# mm8i.net
KiCad netlist of a schematic drawn in EAGLE
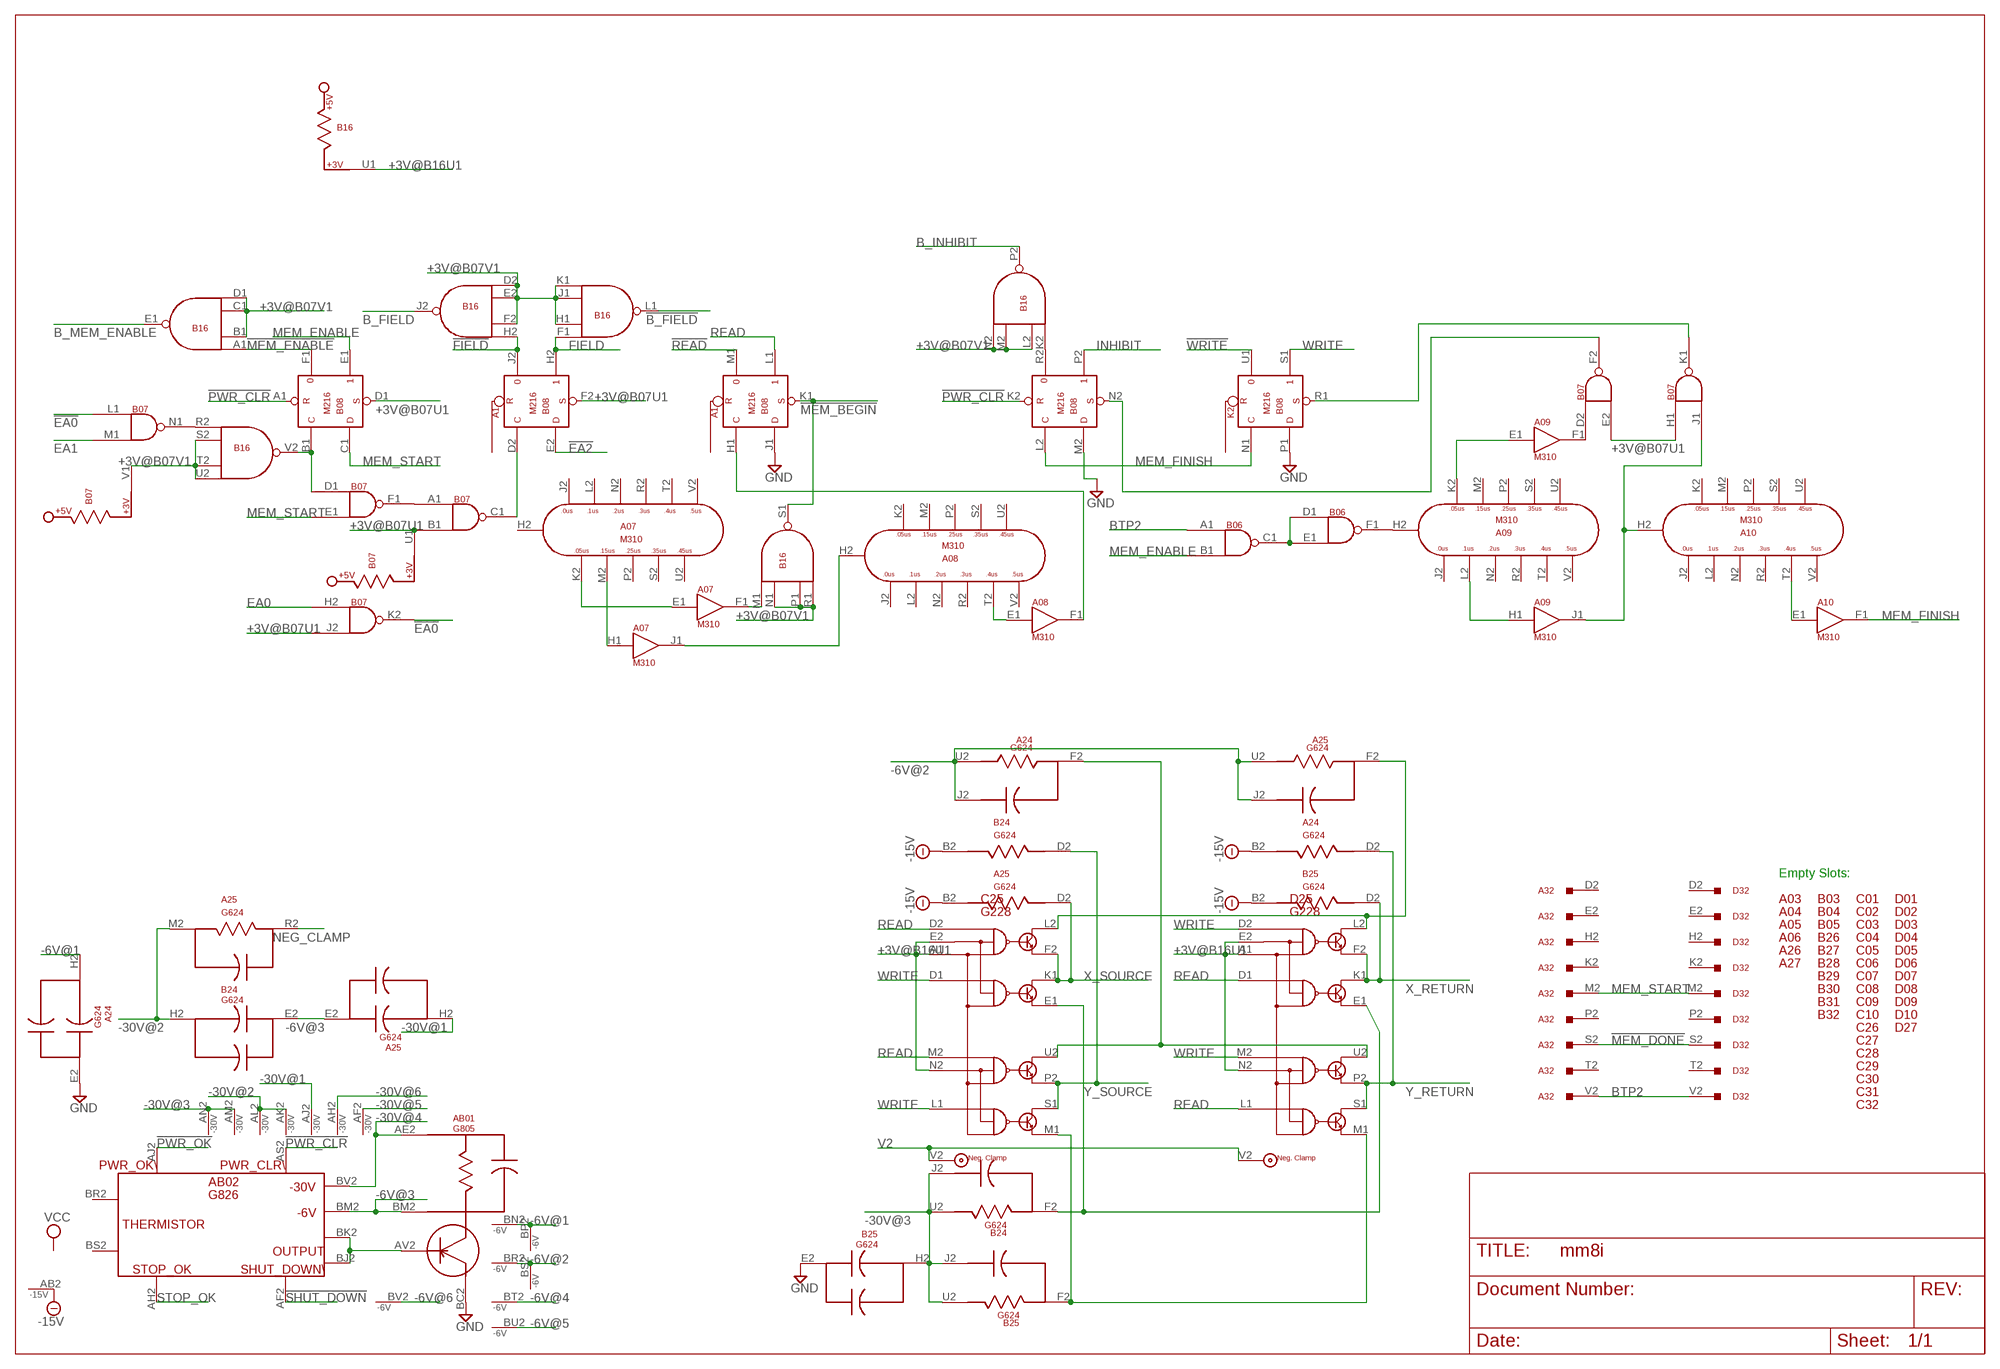
[diagram p0: schematic, sheet 1]

(export (version "E")
  (design (tool "Eeschema 10.0.6"))
  (components
    (comp (ref "A03")
      (value "H807")
      (footprint "eagle-import:H807")
      (libsource (lib "eagle-import") (part "H807"))
    )
    (comp (ref "A04")
      (value "H807")
      (footprint "eagle-import:H807")
      (libsource (lib "eagle-import") (part "H807"))
    )
    (comp (ref "A05")
      (value "H807")
      (footprint "eagle-import:H807")
      (libsource (lib "eagle-import") (part "H807"))
    )
    (comp (ref "A06")
      (value "H807")
      (footprint "eagle-import:H807")
      (libsource (lib "eagle-import") (part "H807"))
    )
    (comp (ref "A07")
      (value "M310")
      (footprint "eagle-import:H807")
      (libsource (lib "eagle-import") (part "M310"))
    )
    (comp (ref "A08")
      (value "M310")
      (footprint "eagle-import:H807")
      (libsource (lib "eagle-import") (part "M310"))
    )
    (comp (ref "A09")
      (value "M310")
      (footprint "eagle-import:H807")
      (libsource (lib "eagle-import") (part "M310"))
    )
    (comp (ref "A10")
      (value "M310")
      (footprint "eagle-import:H807")
      (libsource (lib "eagle-import") (part "M310"))
    )
    (comp (ref "A24")
      (value "G624")
      (footprint "eagle-import:H807")
      (libsource (lib "eagle-import") (part "G624"))
    )
    (comp (ref "A25")
      (value "G624")
      (footprint "eagle-import:H807")
      (libsource (lib "eagle-import") (part "G624"))
    )
    (comp (ref "A26")
      (value "H807")
      (footprint "eagle-import:H807")
      (libsource (lib "eagle-import") (part "H807"))
    )
    (comp (ref "A27")
      (value "H807")
      (footprint "eagle-import:H807")
      (libsource (lib "eagle-import") (part "H807"))
    )
    (comp (ref "A32")
      (value "W033")
      (footprint "eagle-import:H807")
      (libsource (lib "eagle-import") (part "W011"))
    )
    (comp (ref "AB01")
      (value "G805")
      (footprint "eagle-import:H807-2")
      (libsource (lib "eagle-import") (part "G805"))
    )
    (comp (ref "AB02")
      (value "G826")
      (footprint "eagle-import:H807-2")
      (libsource (lib "eagle-import") (part "G826"))
    )
    (comp (ref "B03")
      (value "H807")
      (footprint "eagle-import:H807")
      (libsource (lib "eagle-import") (part "H807"))
    )
    (comp (ref "B04")
      (value "H807")
      (footprint "eagle-import:H807")
      (libsource (lib "eagle-import") (part "H807"))
    )
    (comp (ref "B05")
      (value "H807")
      (footprint "eagle-import:H807")
      (libsource (lib "eagle-import") (part "H807"))
    )
    (comp (ref "B06")
      (value "M113")
      (footprint "eagle-import:H807")
      (libsource (lib "eagle-import") (part "M113"))
    )
    (comp (ref "B07")
      (value "M113")
      (footprint "eagle-import:H807")
      (libsource (lib "eagle-import") (part "M113"))
    )
    (comp (ref "B08")
      (value "M216")
      (footprint "eagle-import:H807")
      (libsource (lib "eagle-import") (part "M206X"))
    )
    (comp (ref "B16")
      (value "M617")
      (footprint "eagle-import:H807")
      (libsource (lib "eagle-import") (part "M617"))
    )
    (comp (ref "B24")
      (value "G624")
      (footprint "eagle-import:H807")
      (libsource (lib "eagle-import") (part "G624"))
    )
    (comp (ref "B25")
      (value "G624")
      (footprint "eagle-import:H807")
      (libsource (lib "eagle-import") (part "G624"))
    )
    (comp (ref "B26")
      (value "H807")
      (footprint "eagle-import:H807")
      (libsource (lib "eagle-import") (part "H807"))
    )
    (comp (ref "B27")
      (value "H807")
      (footprint "eagle-import:H807")
      (libsource (lib "eagle-import") (part "H807"))
    )
    (comp (ref "B28")
      (value "H807")
      (footprint "eagle-import:H807")
      (libsource (lib "eagle-import") (part "H807"))
    )
    (comp (ref "B29")
      (value "H807")
      (footprint "eagle-import:H807")
      (libsource (lib "eagle-import") (part "H807"))
    )
    (comp (ref "B30")
      (value "H807")
      (footprint "eagle-import:H807")
      (libsource (lib "eagle-import") (part "H807"))
    )
    (comp (ref "B31")
      (value "H807")
      (footprint "eagle-import:H807")
      (libsource (lib "eagle-import") (part "H807"))
    )
    (comp (ref "B32")
      (value "H807")
      (footprint "eagle-import:H807")
      (libsource (lib "eagle-import") (part "H807"))
    )
    (comp (ref "C01")
      (value "H807")
      (footprint "eagle-import:H807")
      (libsource (lib "eagle-import") (part "H807"))
    )
    (comp (ref "C02")
      (value "H807")
      (footprint "eagle-import:H807")
      (libsource (lib "eagle-import") (part "H807"))
    )
    (comp (ref "C03")
      (value "H807")
      (footprint "eagle-import:H807")
      (libsource (lib "eagle-import") (part "H807"))
    )
    (comp (ref "C04")
      (value "H807")
      (footprint "eagle-import:H807")
      (libsource (lib "eagle-import") (part "H807"))
    )
    (comp (ref "C05")
      (value "H807")
      (footprint "eagle-import:H807")
      (libsource (lib "eagle-import") (part "H807"))
    )
    (comp (ref "C06")
      (value "H807")
      (footprint "eagle-import:H807")
      (libsource (lib "eagle-import") (part "H807"))
    )
    (comp (ref "C07")
      (value "H807")
      (footprint "eagle-import:H807")
      (libsource (lib "eagle-import") (part "H807"))
    )
    (comp (ref "C08")
      (value "H807")
      (footprint "eagle-import:H807")
      (libsource (lib "eagle-import") (part "H807"))
    )
    (comp (ref "C09")
      (value "H807")
      (footprint "eagle-import:H807")
      (libsource (lib "eagle-import") (part "H807"))
    )
    (comp (ref "C10")
      (value "H807")
      (footprint "eagle-import:H807")
      (libsource (lib "eagle-import") (part "H807"))
    )
    (comp (ref "C25")
      (value "G228")
      (footprint "eagle-import:H807")
      (libsource (lib "eagle-import") (part "G228"))
    )
    (comp (ref "C26")
      (value "H807")
      (footprint "eagle-import:H807")
      (libsource (lib "eagle-import") (part "H807"))
    )
    (comp (ref "C27")
      (value "H807")
      (footprint "eagle-import:H807")
      (libsource (lib "eagle-import") (part "H807"))
    )
    (comp (ref "C28")
      (value "H807")
      (footprint "eagle-import:H807")
      (libsource (lib "eagle-import") (part "H807"))
    )
    (comp (ref "C29")
      (value "H807")
      (footprint "eagle-import:H807")
      (libsource (lib "eagle-import") (part "H807"))
    )
    (comp (ref "C30")
      (value "H807")
      (footprint "eagle-import:H807")
      (libsource (lib "eagle-import") (part "H807"))
    )
    (comp (ref "C31")
      (value "H807")
      (footprint "eagle-import:H807")
      (libsource (lib "eagle-import") (part "H807"))
    )
    (comp (ref "C32")
      (value "H807")
      (footprint "eagle-import:H807")
      (libsource (lib "eagle-import") (part "H807"))
    )
    (comp (ref "D01")
      (value "H807")
      (footprint "eagle-import:H807")
      (libsource (lib "eagle-import") (part "H807"))
    )
    (comp (ref "D02")
      (value "H807")
      (footprint "eagle-import:H807")
      (libsource (lib "eagle-import") (part "H807"))
    )
    (comp (ref "D03")
      (value "H807")
      (footprint "eagle-import:H807")
      (libsource (lib "eagle-import") (part "H807"))
    )
    (comp (ref "D04")
      (value "H807")
      (footprint "eagle-import:H807")
      (libsource (lib "eagle-import") (part "H807"))
    )
    (comp (ref "D05")
      (value "H807")
      (footprint "eagle-import:H807")
      (libsource (lib "eagle-import") (part "H807"))
    )
    (comp (ref "D06")
      (value "H807")
      (footprint "eagle-import:H807")
      (libsource (lib "eagle-import") (part "H807"))
    )
    (comp (ref "D07")
      (value "H807")
      (footprint "eagle-import:H807")
      (libsource (lib "eagle-import") (part "H807"))
    )
    (comp (ref "D08")
      (value "H807")
      (footprint "eagle-import:H807")
      (libsource (lib "eagle-import") (part "H807"))
    )
    (comp (ref "D09")
      (value "H807")
      (footprint "eagle-import:H807")
      (libsource (lib "eagle-import") (part "H807"))
    )
    (comp (ref "D10")
      (value "H807")
      (footprint "eagle-import:H807")
      (libsource (lib "eagle-import") (part "H807"))
    )
    (comp (ref "D25")
      (value "G228")
      (footprint "eagle-import:H807")
      (libsource (lib "eagle-import") (part "G228"))
    )
    (comp (ref "D27")
      (value "H807")
      (footprint "eagle-import:H807")
      (libsource (lib "eagle-import") (part "H807"))
    )
    (comp (ref "D32")
      (value "W033")
      (footprint "eagle-import:H807")
      (libsource (lib "eagle-import") (part "W011"))
    )
  )
  (nets
    (net (code "1") (name "-15V") (class "Default")
      (node (ref "A24") (pin "B2") (pinfunction "P$1_B2") (pintype "passive"))
      (node (ref "A25") (pin "B2") (pinfunction "P$1_B2") (pintype "passive"))
      (node (ref "AB02") (pin "AB2") (pinfunction "-15V_AB2") (pintype "power_in"))
      (node (ref "B24") (pin "B2") (pinfunction "P$1_B2") (pintype "passive"))
      (node (ref "B25") (pin "B2") (pinfunction "P$1_B2") (pintype "passive"))
    )
    (net (code "2") (name "/+3V@B07U1") (class "Default")
      (node (ref "B07") (pin "B1") (pinfunction "IN2_B1") (pintype "input"))
      (node (ref "B07") (pin "E2") (pinfunction "IN2_E2") (pintype "input"))
      (node (ref "B07") (pin "H1") (pinfunction "IN1_H1") (pintype "input"))
      (node (ref "B07") (pin "J2") (pinfunction "IN2_J2") (pintype "input"))
      (node (ref "B07") (pin "U1") (pinfunction "P$1_U1") (pintype "passive"))
      (node (ref "B08") (pin "D1") (pinfunction "S_D1") (pintype "input"))
      (node (ref "B08") (pin "F2") (pinfunction "S_F2") (pintype "input"))
    )
    (net (code "3") (name "/+3V@B07V1") (class "Default")
      (node (ref "B07") (pin "V1") (pinfunction "P$1_V1") (pintype "passive"))
      (node (ref "B16") (pin "B1") (pinfunction "IN2_B1") (pintype "input"))
      (node (ref "B16") (pin "C1") (pinfunction "IN3_C1") (pintype "input"))
      (node (ref "B16") (pin "D1") (pinfunction "IN4_D1") (pintype "input"))
      (node (ref "B16") (pin "D2") (pinfunction "IN1_D2") (pintype "input"))
      (node (ref "B16") (pin "E2") (pinfunction "IN2_E2") (pintype "input"))
      (node (ref "B16") (pin "F2") (pinfunction "IN3_F2") (pintype "input"))
      (node (ref "B16") (pin "H1") (pinfunction "IN2_H1") (pintype "input"))
      (node (ref "B16") (pin "J1") (pinfunction "IN3_J1") (pintype "input"))
      (node (ref "B16") (pin "K1") (pinfunction "IN4_K1") (pintype "input"))
      (node (ref "B16") (pin "L2") (pinfunction "IN2_L2") (pintype "input"))
      (node (ref "B16") (pin "M2") (pinfunction "IN3_M2") (pintype "input"))
      (node (ref "B16") (pin "N1") (pinfunction "IN2_N1") (pintype "input"))
      (node (ref "B16") (pin "N2") (pinfunction "IN4_N2") (pintype "input"))
      (node (ref "B16") (pin "P1") (pinfunction "IN3_P1") (pintype "input"))
      (node (ref "B16") (pin "R1") (pinfunction "IN4_R1") (pintype "input"))
      (node (ref "B16") (pin "S2") (pinfunction "IN2_S2") (pintype "input"))
      (node (ref "B16") (pin "T2") (pinfunction "IN3_T2") (pintype "input"))
      (node (ref "B16") (pin "U2") (pinfunction "IN4_U2") (pintype "input"))
    )
    (net (code "4") (name "/+3V@B16U1") (class "Default")
      (node (ref "B16") (pin "U1") (pinfunction "P$1_U1") (pintype "passive"))
      (node (ref "C25") (pin "A1") (pinfunction "A1_A1") (pintype "input"))
      (node (ref "C25") (pin "E2") (pinfunction "E2_E2") (pintype "input"))
      (node (ref "C25") (pin "N2") (pinfunction "N2_N2") (pintype "input"))
      (node (ref "D25") (pin "A1") (pinfunction "A1_A1") (pintype "input"))
      (node (ref "D25") (pin "E2") (pinfunction "E2_E2") (pintype "input"))
      (node (ref "D25") (pin "N2") (pinfunction "N2_N2") (pintype "input"))
    )
    (net (code "5") (name "/-6V@1") (class "Default")
      (node (ref "A24") (pin "H2") (pinfunction "P$1_H2") (pintype "passive"))
      (node (ref "AB01") (pin "BN2") (pinfunction "-6V_BN2") (pintype "power_in"))
      (node (ref "AB01") (pin "BP2") (pinfunction "-6V_BP2") (pintype "power_in"))
    )
    (net (code "6") (name "/-6V@2") (class "Default")
      (node (ref "A24") (pin "J2") (pinfunction "P$3_J2") (pintype "passive"))
      (node (ref "A24") (pin "U2") (pinfunction "P$2_U2") (pintype "passive"))
      (node (ref "A25") (pin "J2") (pinfunction "P$3_J2") (pintype "passive"))
      (node (ref "A25") (pin "U2") (pinfunction "P$2_U2") (pintype "passive"))
      (node (ref "AB01") (pin "BR2") (pinfunction "-6V_BR2") (pintype "power_in"))
      (node (ref "AB01") (pin "BS2") (pinfunction "-6V_BS2") (pintype "power_in"))
    )
    (net (code "7") (name "/-6V@3") (class "Default")
      (node (ref "A25") (pin "E2") (pinfunction "P$2_E2") (pintype "passive"))
      (node (ref "AB01") (pin "BM2") (pinfunction "-6V_BM2") (pintype "power_in"))
      (node (ref "AB02") (pin "BM2") (pinfunction "-6V_BM2") (pintype "power_in"))
      (node (ref "B24") (pin "E2") (pinfunction "P$2_E2") (pintype "passive"))
    )
    (net (code "8") (name "/-6V@4") (class "Default")
      (node (ref "AB01") (pin "BT2") (pinfunction "-6V_BT2") (pintype "power_in"))
    )
    (net (code "9") (name "/-6V@5") (class "Default")
      (node (ref "AB01") (pin "BU2") (pinfunction "-6V_BU2") (pintype "power_in"))
    )
    (net (code "10") (name "/-6V@6") (class "Default")
      (node (ref "AB01") (pin "BV2") (pinfunction "-6V_BV2") (pintype "power_in"))
    )
    (net (code "11") (name "/-30V@1") (class "Default")
      (node (ref "A25") (pin "H2") (pinfunction "P$1_H2") (pintype "passive"))
      (node (ref "AB01") (pin "AJ2") (pinfunction "-30V_AJ2") (pintype "power_in"))
    )
    (net (code "12") (name "/-30V@2") (class "Default")
      (node (ref "A25") (pin "M2") (pinfunction "P$1_M2") (pintype "passive"))
      (node (ref "AB01") (pin "AK2") (pinfunction "-30V_AK2") (pintype "power_in"))
      (node (ref "AB01") (pin "AL2") (pinfunction "-30V_AL2") (pintype "power_in"))
      (node (ref "B24") (pin "H2") (pinfunction "P$1_H2") (pintype "passive"))
    )
    (net (code "13") (name "/-30V@3") (class "Default")
      (node (ref "AB01") (pin "AM2") (pinfunction "-30V_AM2") (pintype "power_in"))
      (node (ref "AB01") (pin "AN2") (pinfunction "-30V_AN2") (pintype "power_in"))
      (node (ref "B24") (pin "J2") (pinfunction "P$3_J2") (pintype "passive"))
      (node (ref "B24") (pin "U2") (pinfunction "P$2_U2") (pintype "passive"))
      (node (ref "B25") (pin "H2") (pinfunction "P$1_H2") (pintype "passive"))
      (node (ref "B25") (pin "J2") (pinfunction "P$3_J2") (pintype "passive"))
      (node (ref "B25") (pin "U2") (pinfunction "P$2_U2") (pintype "passive"))
    )
    (net (code "14") (name "/-30V@4") (class "Default")
      (node (ref "AB01") (pin "AE2") (pinfunction "-30V_AE2") (pintype "power_in"))
      (node (ref "AB02") (pin "BV2") (pinfunction "-30V_BV2") (pintype "power_in"))
    )
    (net (code "15") (name "/-30V@5") (class "Default")
      (node (ref "AB01") (pin "AF2") (pinfunction "-30V_AF2") (pintype "power_in"))
    )
    (net (code "16") (name "/-30V@6") (class "Default")
      (node (ref "AB01") (pin "AH2") (pinfunction "-30V_AH2") (pintype "power_in"))
    )
    (net (code "17") (name "/BTP2") (class "Default")
      (node (ref "A32") (pin "V2") (pinfunction "P$2_V2") (pintype "bidirectional"))
      (node (ref "B06") (pin "A1") (pinfunction "IN1_A1") (pintype "input"))
      (node (ref "D32") (pin "V2") (pinfunction "P$2_V2") (pintype "bidirectional"))
    )
    (net (code "18") (name "/B_FIELD") (class "Default")
      (node (ref "B16") (pin "J2") (pinfunction "OUT_J2") (pintype "open_collector"))
    )
    (net (code "19") (name "/B_INHIBIT") (class "Default")
      (node (ref "B16") (pin "P2") (pinfunction "OUT_P2") (pintype "open_collector"))
    )
    (net (code "20") (name "/B_MEM_ENABLE") (class "Default")
      (node (ref "B16") (pin "E1") (pinfunction "OUT_E1") (pintype "open_collector"))
    )
    (net (code "21") (name "/EA0") (class "Default")
      (node (ref "B07") (pin "H2") (pinfunction "IN1_H2") (pintype "input"))
    )
    (net (code "22") (name "/EA1") (class "Default")
      (node (ref "B07") (pin "M1") (pinfunction "IN2_M1") (pintype "input"))
    )
    (net (code "23") (name "/FIELD") (class "Default")
      (node (ref "B08") (pin "H2") (pinfunction "1_H2") (pintype "output"))
      (node (ref "B16") (pin "F1") (pinfunction "IN1_F1") (pintype "input"))
    )
    (net (code "24") (name "/INHIBIT") (class "Default")
      (node (ref "B08") (pin "P2") (pinfunction "1_P2") (pintype "output"))
    )
    (net (code "25") (name "/MEM_ENABLE") (class "Default")
      (node (ref "B06") (pin "B1") (pinfunction "IN2_B1") (pintype "input"))
      (node (ref "B08") (pin "E1") (pinfunction "1_E1") (pintype "output"))
    )
    (net (code "26") (name "/MEM_FINISH") (class "Default")
      (node (ref "A10") (pin "F1") (pinfunction "OUT_F1") (pintype "output"))
      (node (ref "B08") (pin "L2") (pinfunction "C_L2") (pintype "input"))
      (node (ref "B08") (pin "N1") (pinfunction "C_N1") (pintype "input"))
    )
    (net (code "27") (name "/MEM_START") (class "Default")
      (node (ref "A32") (pin "M2") (pinfunction "P$2_M2") (pintype "bidirectional"))
      (node (ref "B07") (pin "E1") (pinfunction "IN2_E1") (pintype "input"))
      (node (ref "B08") (pin "C1") (pinfunction "D_C1") (pintype "input"))
      (node (ref "D32") (pin "M2") (pinfunction "P$2_M2") (pintype "bidirectional"))
    )
    (net (code "28") (name "/NEG_CLAMP") (class "Default")
      (node (ref "A25") (pin "R2") (pinfunction "P$2_R2") (pintype "passive"))
    )
    (net (code "29") (name "/READ") (class "Default")
      (node (ref "B08") (pin "L1") (pinfunction "1_L1") (pintype "output"))
      (node (ref "C25") (pin "D2") (pinfunction "D2_D2") (pintype "input"))
      (node (ref "C25") (pin "M2") (pinfunction "M2_M2") (pintype "input"))
      (node (ref "D25") (pin "D1") (pinfunction "D1_D1") (pintype "input"))
      (node (ref "D25") (pin "L1") (pinfunction "L1_L1") (pintype "input"))
    )
    (net (code "30") (name "/STOP_OK") (class "Default")
      (node (ref "AB02") (pin "AH2") (pinfunction "AH2_AH2") (pintype "input"))
    )
    (net (code "31") (name "/V2") (class "Default")
      (node (ref "C25") (pin "V2") (pinfunction "V2_V2") (pintype "input"))
      (node (ref "D25") (pin "V2") (pinfunction "V2_V2") (pintype "input"))
    )
    (net (code "32") (name "/WRITE") (class "Default")
      (node (ref "B08") (pin "S1") (pinfunction "1_S1") (pintype "output"))
      (node (ref "C25") (pin "D1") (pinfunction "D1_D1") (pintype "input"))
      (node (ref "C25") (pin "L1") (pinfunction "L1_L1") (pintype "input"))
      (node (ref "D25") (pin "D2") (pinfunction "D2_D2") (pintype "input"))
      (node (ref "D25") (pin "M2") (pinfunction "M2_M2") (pintype "input"))
    )
    (net (code "33") (name "/X_RETURN") (class "Default")
      (node (ref "B25") (pin "D2") (pinfunction "P$2_D2") (pintype "passive"))
      (node (ref "D25") (pin "F2") (pinfunction "F2_F2") (pintype "passive"))
      (node (ref "D25") (pin "K1") (pinfunction "K1_K1") (pintype "passive"))
    )
    (net (code "34") (name "/X_SOURCE") (class "Default")
      (node (ref "A25") (pin "D2") (pinfunction "P$2_D2") (pintype "passive"))
      (node (ref "C25") (pin "F2") (pinfunction "F2_F2") (pintype "passive"))
      (node (ref "C25") (pin "K1") (pinfunction "K1_K1") (pintype "passive"))
    )
    (net (code "35") (name "/Y_RETURN") (class "Default")
      (node (ref "A24") (pin "D2") (pinfunction "P$2_D2") (pintype "passive"))
      (node (ref "D25") (pin "P2") (pinfunction "P2_P2") (pintype "passive"))
      (node (ref "D25") (pin "S1") (pinfunction "S1_S1") (pintype "passive"))
    )
    (net (code "36") (name "/Y_SOURCE") (class "Default")
      (node (ref "B24") (pin "D2") (pinfunction "P$2_D2") (pintype "passive"))
      (node (ref "C25") (pin "P2") (pinfunction "P2_P2") (pintype "passive"))
      (node (ref "C25") (pin "S1") (pinfunction "S1_S1") (pintype "passive"))
    )
    (net (code "37") (name "/~{B_FIELD}") (class "Default")
      (node (ref "B16") (pin "L1") (pinfunction "OUT_L1") (pintype "open_collector"))
    )
    (net (code "38") (name "/~{EA0}") (class "Default")
      (node (ref "B07") (pin "K2") (pinfunction "OUT_K2") (pintype "output"))
      (node (ref "B07") (pin "L1") (pinfunction "IN1_L1") (pintype "input"))
    )
    (net (code "39") (name "/~{EA2}") (class "Default")
      (node (ref "B08") (pin "E2") (pinfunction "D_E2") (pintype "input"))
    )
    (net (code "40") (name "/~{FIELD}") (class "Default")
      (node (ref "B08") (pin "J2") (pinfunction "0_J2") (pintype "output"))
      (node (ref "B16") (pin "H2") (pinfunction "IN4_H2") (pintype "input"))
    )
    (net (code "41") (name "/~{MEM_BEGIN}") (class "Default")
      (node (ref "B08") (pin "K1") (pinfunction "S_K1") (pintype "input"))
      (node (ref "B16") (pin "S1") (pinfunction "OUT_S1") (pintype "open_collector"))
    )
    (net (code "42") (name "/~{MEM_DONE}") (class "Default")
      (node (ref "A32") (pin "S2") (pinfunction "P$2_S2") (pintype "bidirectional"))
      (node (ref "D32") (pin "S2") (pinfunction "P$2_S2") (pintype "bidirectional"))
    )
    (net (code "43") (name "/~{MEM_ENABLE}") (class "Default")
      (node (ref "B08") (pin "F1") (pinfunction "0_F1") (pintype "output"))
      (node (ref "B16") (pin "A1") (pinfunction "IN1_A1") (pintype "input"))
    )
    (net (code "44") (name "/~{PWR_CLR}") (class "Default")
      (node (ref "AB02") (pin "AS2") (pinfunction "AS2_AS2") (pintype "bidirectional"))
      (node (ref "B08") (pin "A1") (pinfunction "R_A1") (pintype "input"))
      (node (ref "B08") (pin "K2") (pinfunction "R_K2") (pintype "input"))
    )
    (net (code "45") (name "/~{PWR_OK}") (class "Default")
      (node (ref "AB02") (pin "AJ2") (pinfunction "AJ2_AJ2") (pintype "bidirectional"))
    )
    (net (code "46") (name "/~{READ}") (class "Default")
      (node (ref "B08") (pin "M1") (pinfunction "0_M1") (pintype "output"))
    )
    (net (code "47") (name "/~{SHUT_DOWN}") (class "Default")
      (node (ref "AB02") (pin "AF2") (pinfunction "AF2_AF2") (pintype "output"))
    )
    (net (code "48") (name "/~{WRITE}") (class "Default")
      (node (ref "B08") (pin "U1") (pinfunction "0_U1") (pintype "output"))
    )
    (net (code "49") (name "GND") (class "Default")
      (node (ref "A24") (pin "E2") (pinfunction "P$2_E2") (pintype "passive"))
      (node (ref "AB01") (pin "BC2") (pinfunction "GND_BC2") (pintype "power_in"))
      (node (ref "B08") (pin "J1") (pinfunction "D_J1") (pintype "input"))
      (node (ref "B08") (pin "M2") (pinfunction "D_M2") (pintype "input"))
      (node (ref "B08") (pin "P1") (pinfunction "D_P1") (pintype "input"))
      (node (ref "B25") (pin "E2") (pinfunction "P$2_E2") (pintype "passive"))
    )
    (net (code "50") (name "Net-(A07A-IN)") (class "Default")
      (node (ref "A07") (pin "E1") (pinfunction "IN_E1") (pintype "input"))
      (node (ref "A07") (pin "K2") (pinfunction "K2_K2") (pintype "output"))
    )
    (net (code "51") (name "Net-(A07A-OUT)") (class "Default")
      (node (ref "A07") (pin "F1") (pinfunction "OUT_F1") (pintype "output"))
      (node (ref "B16") (pin "M1") (pinfunction "IN1_M1") (pintype "input"))
    )
    (net (code "52") (name "Net-(A07E-IN)") (class "Default")
      (node (ref "A07") (pin "H1") (pinfunction "IN_H1") (pintype "input"))
      (node (ref "A07") (pin "M2") (pinfunction "M2_M2") (pintype "output"))
    )
    (net (code "53") (name "Net-(A07E-OUT)") (class "Default")
      (node (ref "A07") (pin "J1") (pinfunction "OUT_J1") (pintype "output"))
      (node (ref "A08") (pin "H2") (pinfunction "H2_H2") (pintype "input"))
    )
    (net (code "54") (name "Net-(A08A-IN)") (class "Default")
      (node (ref "A08") (pin "E1") (pinfunction "IN_E1") (pintype "input"))
      (node (ref "A08") (pin "T2") (pinfunction "T2_T2") (pintype "output"))
    )
    (net (code "55") (name "Net-(A08A-OUT)") (class "Default")
      (node (ref "A08") (pin "F1") (pinfunction "OUT_F1") (pintype "output"))
      (node (ref "B08") (pin "H1") (pinfunction "C_H1") (pintype "input"))
    )
    (net (code "56") (name "Net-(A09A-IN)") (class "Default")
      (node (ref "A09") (pin "E1") (pinfunction "IN_E1") (pintype "input"))
      (node (ref "A09") (pin "K2") (pinfunction "K2_K2") (pintype "output"))
    )
    (net (code "57") (name "Net-(A09A-OUT)") (class "Default")
      (node (ref "A09") (pin "F1") (pinfunction "OUT_F1") (pintype "output"))
      (node (ref "B07") (pin "D2") (pinfunction "IN1_D2") (pintype "input"))
    )
    (net (code "58") (name "Net-(A09E-IN)") (class "Default")
      (node (ref "A09") (pin "H1") (pinfunction "IN_H1") (pintype "input"))
      (node (ref "A09") (pin "L2") (pinfunction "L2_L2") (pintype "output"))
    )
    (net (code "59") (name "Net-(A09E-OUT)") (class "Default")
      (node (ref "A09") (pin "J1") (pinfunction "OUT_J1") (pintype "output"))
      (node (ref "A10") (pin "H2") (pinfunction "H2_H2") (pintype "input"))
      (node (ref "B07") (pin "J1") (pinfunction "IN2_J1") (pintype "input"))
    )
    (net (code "60") (name "Net-(A10A-IN)") (class "Default")
      (node (ref "A10") (pin "E1") (pinfunction "IN_E1") (pintype "input"))
      (node (ref "A10") (pin "T2") (pinfunction "T2_T2") (pintype "output"))
    )
    (net (code "61") (name "Net-(A24H-P$1)") (class "Default")
      (node (ref "A24") (pin "F2") (pinfunction "P$1_F2") (pintype "passive"))
      (node (ref "C25") (pin "U2") (pinfunction "U2_U2") (pintype "passive"))
      (node (ref "D25") (pin "U2") (pinfunction "U2_U2") (pintype "passive"))
    )
    (net (code "62") (name "Net-(A25H-P$1)") (class "Default")
      (node (ref "A25") (pin "F2") (pinfunction "P$1_F2") (pintype "passive"))
      (node (ref "C25") (pin "L2") (pinfunction "L2_L2") (pintype "passive"))
      (node (ref "D25") (pin "L2") (pinfunction "L2_L2") (pintype "passive"))
    )
    (net (code "63") (name "Net-(AB01-PadAV2)") (class "Default")
      (node (ref "AB01") (pin "AV2") (pinfunction "AV2_AV2") (pintype "input"))
      (node (ref "AB02") (pin "BJ2") (pinfunction "BJ2_BJ2") (pintype "output"))
      (node (ref "AB02") (pin "BK2") (pinfunction "BK2_BK2") (pintype "passive"))
    )
    (net (code "64") (name "Net-(B06A-OUT)") (class "Default")
      (node (ref "B06") (pin "C1") (pinfunction "OUT_C1") (pintype "output"))
      (node (ref "B06") (pin "D1") (pinfunction "IN1_D1") (pintype "input"))
      (node (ref "B06") (pin "E1") (pinfunction "IN2_E1") (pintype "input"))
    )
    (net (code "65") (name "Net-(B06B-OUT)") (class "Default")
      (node (ref "A09") (pin "H2") (pinfunction "H2_H2") (pintype "input"))
      (node (ref "B06") (pin "F1") (pinfunction "OUT_F1") (pintype "output"))
    )
    (net (code "66") (name "Net-(B07A-IN1)") (class "Default")
      (node (ref "B07") (pin "A1") (pinfunction "IN1_A1") (pintype "input"))
      (node (ref "B07") (pin "F1") (pinfunction "OUT_F1") (pintype "output"))
    )
    (net (code "67") (name "Net-(B07A-OUT)") (class "Default")
      (node (ref "B07") (pin "C1") (pinfunction "OUT_C1") (pintype "output"))
      (node (ref "B08") (pin "D2") (pinfunction "C_D2") (pintype "input"))
    )
    (net (code "68") (name "Net-(B07B-IN1)") (class "Default")
      (node (ref "B07") (pin "D1") (pinfunction "IN1_D1") (pintype "input"))
      (node (ref "B08") (pin "B1") (pinfunction "C_B1") (pintype "input"))
      (node (ref "B16") (pin "V2") (pinfunction "OUT_V2") (pintype "open_collector"))
    )
    (net (code "69") (name "Net-(B07C-OUT)") (class "Default")
      (node (ref "B07") (pin "F2") (pinfunction "OUT_F2") (pintype "output"))
      (node (ref "B08") (pin "N2") (pinfunction "S_N2") (pintype "input"))
    )
    (net (code "70") (name "Net-(B07F-OUT)") (class "Default")
      (node (ref "B07") (pin "K1") (pinfunction "OUT_K1") (pintype "output"))
      (node (ref "B08") (pin "R1") (pinfunction "S_R1") (pintype "input"))
    )
    (net (code "71") (name "Net-(B07H-OUT)") (class "Default")
      (node (ref "B07") (pin "N1") (pinfunction "OUT_N1") (pintype "output"))
      (node (ref "B16") (pin "R2") (pinfunction "IN1_R2") (pintype "input"))
    )
    (net (code "72") (name "Net-(B08F-0)") (class "Default")
      (node (ref "B08") (pin "R2") (pinfunction "0_R2") (pintype "output"))
      (node (ref "B16") (pin "K2") (pinfunction "IN1_K2") (pintype "input"))
    )
    (net (code "73") (name "Net-(B24H-P$1)") (class "Default")
      (node (ref "B24") (pin "F2") (pinfunction "P$1_F2") (pintype "passive"))
      (node (ref "C25") (pin "E1") (pinfunction "E1_E1") (pintype "passive"))
      (node (ref "D25") (pin "E1") (pinfunction "E1_E1") (pintype "passive"))
    )
    (net (code "74") (name "Net-(B25H-P$1)") (class "Default")
      (node (ref "B25") (pin "F2") (pinfunction "P$1_F2") (pintype "passive"))
      (node (ref "C25") (pin "M1") (pinfunction "M1_M1") (pintype "passive"))
      (node (ref "D25") (pin "M1") (pinfunction "M1_M1") (pintype "passive"))
    )
    (net (code "76") (name "unconnected-(A07-PadH2)") (class "Default")
      (node (ref "A07") (pin "H2") (pinfunction "H2_H2") (pintype "input"))
    )
    (net (code "77") (name "unconnected-(A07-PadJ2)") (class "Default")
      (node (ref "A07") (pin "J2") (pinfunction "J2_J2") (pintype "output"))
    )
    (net (code "78") (name "unconnected-(A07-PadL2)") (class "Default")
      (node (ref "A07") (pin "L2") (pinfunction "L2_L2") (pintype "output"))
    )
    (net (code "79") (name "unconnected-(A07-PadN2)") (class "Default")
      (node (ref "A07") (pin "N2") (pinfunction "N2_N2") (pintype "output"))
    )
    (net (code "80") (name "unconnected-(A07-PadP2)") (class "Default")
      (node (ref "A07") (pin "P2") (pinfunction "P2_P2") (pintype "output"))
    )
    (net (code "81") (name "unconnected-(A07-PadR2)") (class "Default")
      (node (ref "A07") (pin "R2") (pinfunction "R2_R2") (pintype "output"))
    )
    (net (code "82") (name "unconnected-(A07-PadS2)") (class "Default")
      (node (ref "A07") (pin "S2") (pinfunction "S2_S2") (pintype "output"))
    )
    (net (code "83") (name "unconnected-(A07-PadT2)") (class "Default")
      (node (ref "A07") (pin "T2") (pinfunction "T2_T2") (pintype "output"))
    )
    (net (code "84") (name "unconnected-(A07-PadU2)") (class "Default")
      (node (ref "A07") (pin "U2") (pinfunction "U2_U2") (pintype "output"))
    )
    (net (code "85") (name "unconnected-(A07-PadV2)") (class "Default")
      (node (ref "A07") (pin "V2") (pinfunction "V2_V2") (pintype "output"))
    )
    (net (code "86") (name "unconnected-(A08-PadJ2)") (class "Default")
      (node (ref "A08") (pin "J2") (pinfunction "J2_J2") (pintype "output"))
    )
    (net (code "87") (name "unconnected-(A08-PadK2)") (class "Default")
      (node (ref "A08") (pin "K2") (pinfunction "K2_K2") (pintype "output"))
    )
    (net (code "88") (name "unconnected-(A08-PadL2)") (class "Default")
      (node (ref "A08") (pin "L2") (pinfunction "L2_L2") (pintype "output"))
    )
    (net (code "89") (name "unconnected-(A08-PadM2)") (class "Default")
      (node (ref "A08") (pin "M2") (pinfunction "M2_M2") (pintype "output"))
    )
    (net (code "90") (name "unconnected-(A08-PadN2)") (class "Default")
      (node (ref "A08") (pin "N2") (pinfunction "N2_N2") (pintype "output"))
    )
    (net (code "91") (name "unconnected-(A08-PadP2)") (class "Default")
      (node (ref "A08") (pin "P2") (pinfunction "P2_P2") (pintype "output"))
    )
    (net (code "92") (name "unconnected-(A08-PadR2)") (class "Default")
      (node (ref "A08") (pin "R2") (pinfunction "R2_R2") (pintype "output"))
    )
    (net (code "93") (name "unconnected-(A08-PadS2)") (class "Default")
      (node (ref "A08") (pin "S2") (pinfunction "S2_S2") (pintype "output"))
    )
    (net (code "94") (name "unconnected-(A08-PadU2)") (class "Default")
      (node (ref "A08") (pin "U2") (pinfunction "U2_U2") (pintype "output"))
    )
    (net (code "95") (name "unconnected-(A08-PadV2)") (class "Default")
      (node (ref "A08") (pin "V2") (pinfunction "V2_V2") (pintype "output"))
    )
    (net (code "96") (name "unconnected-(A09-PadJ2)") (class "Default")
      (node (ref "A09") (pin "J2") (pinfunction "J2_J2") (pintype "output"))
    )
    (net (code "97") (name "unconnected-(A09-PadM2)") (class "Default")
      (node (ref "A09") (pin "M2") (pinfunction "M2_M2") (pintype "output"))
    )
    (net (code "98") (name "unconnected-(A09-PadN2)") (class "Default")
      (node (ref "A09") (pin "N2") (pinfunction "N2_N2") (pintype "output"))
    )
    (net (code "99") (name "unconnected-(A09-PadP2)") (class "Default")
      (node (ref "A09") (pin "P2") (pinfunction "P2_P2") (pintype "output"))
    )
    (net (code "100") (name "unconnected-(A09-PadR2)") (class "Default")
      (node (ref "A09") (pin "R2") (pinfunction "R2_R2") (pintype "output"))
    )
    (net (code "101") (name "unconnected-(A09-PadS2)") (class "Default")
      (node (ref "A09") (pin "S2") (pinfunction "S2_S2") (pintype "output"))
    )
    (net (code "102") (name "unconnected-(A09-PadT2)") (class "Default")
      (node (ref "A09") (pin "T2") (pinfunction "T2_T2") (pintype "output"))
    )
    (net (code "103") (name "unconnected-(A09-PadU2)") (class "Default")
      (node (ref "A09") (pin "U2") (pinfunction "U2_U2") (pintype "output"))
    )
    (net (code "104") (name "unconnected-(A09-PadV2)") (class "Default")
      (node (ref "A09") (pin "V2") (pinfunction "V2_V2") (pintype "output"))
    )
    (net (code "105") (name "unconnected-(A10-PadJ2)") (class "Default")
      (node (ref "A10") (pin "J2") (pinfunction "J2_J2") (pintype "output"))
    )
    (net (code "106") (name "unconnected-(A10-PadK2)") (class "Default")
      (node (ref "A10") (pin "K2") (pinfunction "K2_K2") (pintype "output"))
    )
    (net (code "107") (name "unconnected-(A10-PadL2)") (class "Default")
      (node (ref "A10") (pin "L2") (pinfunction "L2_L2") (pintype "output"))
    )
    (net (code "108") (name "unconnected-(A10-PadM2)") (class "Default")
      (node (ref "A10") (pin "M2") (pinfunction "M2_M2") (pintype "output"))
    )
    (net (code "109") (name "unconnected-(A10-PadN2)") (class "Default")
      (node (ref "A10") (pin "N2") (pinfunction "N2_N2") (pintype "output"))
    )
    (net (code "110") (name "unconnected-(A10-PadP2)") (class "Default")
      (node (ref "A10") (pin "P2") (pinfunction "P2_P2") (pintype "output"))
    )
    (net (code "111") (name "unconnected-(A10-PadR2)") (class "Default")
      (node (ref "A10") (pin "R2") (pinfunction "R2_R2") (pintype "output"))
    )
    (net (code "112") (name "unconnected-(A10-PadS2)") (class "Default")
      (node (ref "A10") (pin "S2") (pinfunction "S2_S2") (pintype "output"))
    )
    (net (code "113") (name "unconnected-(A10-PadU2)") (class "Default")
      (node (ref "A10") (pin "U2") (pinfunction "U2_U2") (pintype "output"))
    )
    (net (code "114") (name "unconnected-(A10-PadV2)") (class "Default")
      (node (ref "A10") (pin "V2") (pinfunction "V2_V2") (pintype "output"))
    )
    (net (code "115") (name "unconnected-(A32A-P$2-PadD2)") (class "Default")
      (node (ref "A32") (pin "D2") (pinfunction "P$2_D2") (pintype "bidirectional"))
    )
    (net (code "116") (name "unconnected-(A32B-P$2-PadE2)") (class "Default")
      (node (ref "A32") (pin "E2") (pinfunction "P$2_E2") (pintype "bidirectional"))
    )
    (net (code "117") (name "unconnected-(A32J-P$2-PadH2)") (class "Default")
      (node (ref "A32") (pin "H2") (pinfunction "P$2_H2") (pintype "bidirectional"))
    )
    (net (code "118") (name "unconnected-(A32K-P$2-PadK2)") (class "Default")
      (node (ref "A32") (pin "K2") (pinfunction "P$2_K2") (pintype "bidirectional"))
    )
    (net (code "119") (name "unconnected-(A32M-P$2-PadP2)") (class "Default")
      (node (ref "A32") (pin "P2") (pinfunction "P$2_P2") (pintype "bidirectional"))
    )
    (net (code "120") (name "unconnected-(A32O-P$2-PadT2)") (class "Default")
      (node (ref "A32") (pin "T2") (pinfunction "P$2_T2") (pintype "bidirectional"))
    )
    (net (code "121") (name "unconnected-(AB02-PadBR2)") (class "Default")
      (node (ref "AB02") (pin "BR2") (pinfunction "BR2_BR2") (pintype "passive"))
    )
    (net (code "122") (name "unconnected-(AB02-PadBS2)") (class "Default")
      (node (ref "AB02") (pin "BS2") (pinfunction "BS2_BS2") (pintype "passive"))
    )
    (net (code "123") (name "unconnected-(D32A-P$2-PadD2)") (class "Default")
      (node (ref "D32") (pin "D2") (pinfunction "P$2_D2") (pintype "bidirectional"))
    )
    (net (code "124") (name "unconnected-(D32B-P$2-PadE2)") (class "Default")
      (node (ref "D32") (pin "E2") (pinfunction "P$2_E2") (pintype "bidirectional"))
    )
    (net (code "125") (name "unconnected-(D32J-P$2-PadH2)") (class "Default")
      (node (ref "D32") (pin "H2") (pinfunction "P$2_H2") (pintype "bidirectional"))
    )
    (net (code "126") (name "unconnected-(D32K-P$2-PadK2)") (class "Default")
      (node (ref "D32") (pin "K2") (pinfunction "P$2_K2") (pintype "bidirectional"))
    )
    (net (code "127") (name "unconnected-(D32M-P$2-PadP2)") (class "Default")
      (node (ref "D32") (pin "P2") (pinfunction "P$2_P2") (pintype "bidirectional"))
    )
    (net (code "128") (name "unconnected-(D32O-P$2-PadT2)") (class "Default")
      (node (ref "D32") (pin "T2") (pinfunction "P$2_T2") (pintype "bidirectional"))
    )
  )
)
